# LTC4041_Battery_Power_Management_IC.net
KiCad netlist of a schematic drawn in Altium Designer
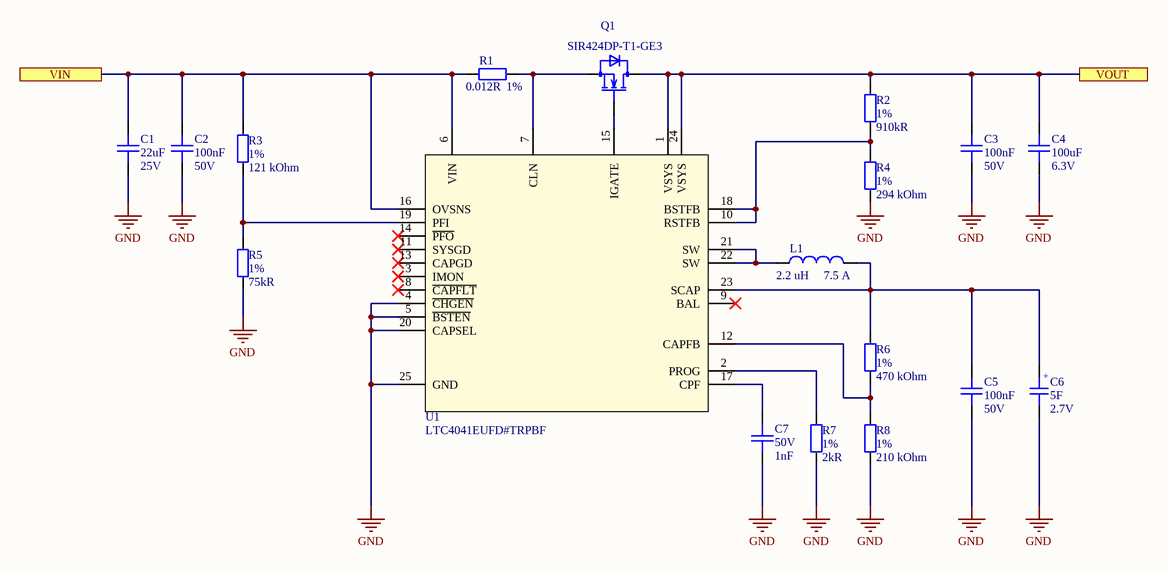
[diagram p0: LTC4041_Battery Power Management IC.SchDoc]

(export (version "E")
  (design (tool "Eeschema 10.0.6"))
  (components
    (comp (ref "C1")
      (value "CAP CER 22UF 25V X5R 0805")
      (footprint "C0805")
      (description "22µF ±20% 25V Ceramic Capacitor X5R 0805 (2012 Metric)")
      (fields
        (field (name "MANUFACTURER") "Yageo")
        (field (name "MANUFACTURER PART NUMBER") "CC0805MKX5R8BB226")
        (field (name "CAPACITANCE") "22uF")
        (field (name "VOLTAGE RATING") "25V")
      )
      (libsource (lib "Control_Board_Model") (part "CAP CER 22UF 25V X5R 0805"))
    )
    (comp (ref "C2")
      (value "CAP CER 0.1UF 50V X7R 0402")
      (footprint "C0402")
      (description "0.1µF ±10% 50V Ceramic Capacitor X7R 0402 (1005 Metric)")
      (fields
        (field (name "MANUFACTURER") "TDK")
        (field (name "MANUFACTURER PART NUMBER") "CGA2B3X7R1H104K050BB")
        (field (name "CAPACITANCE") "100nF")
        (field (name "VOLTAGE") "50V")
      )
      (libsource (lib "Control_Board_Model") (part "CAP CER 0.1UF 50V X7R 0402"))
    )
    (comp (ref "C3")
      (value "CAP CER 0.1UF 50V X7R 0402")
      (footprint "C0402")
      (description "0.1µF ±10% 50V Ceramic Capacitor X7R 0402 (1005 Metric)")
      (fields
        (field (name "MANUFACTURER") "TDK")
        (field (name "MANUFACTURER PART NUMBER") "CGA2B3X7R1H104K050BB")
        (field (name "CAPACITANCE") "100nF")
        (field (name "VOLTAGE") "50V")
      )
      (libsource (lib "Control_Board_Model") (part "CAP CER 0.1UF 50V X7R 0402"))
    )
    (comp (ref "C4")
      (value "CAP CER 100UF 6.3V X5R 1206")
      (footprint "C1206")
      (description "100 µF ±20% 6.3V Ceramic Capacitor X5R 1206 (3216 Metric)")
      (fields
        (field (name "MANUFACTURER") "Yageo")
        (field (name "MANUFACTURER PART NUMBER") "CC1206MKX5R5BB107")
        (field (name "CAPACITANCE") "100uF")
        (field (name "VOLTAGE RATING") "6.3V")
      )
      (libsource (lib "Control_Board_Model") (part "CAP CER 100UF 6.3V X5R 1206"))
    )
    (comp (ref "C5")
      (value "CAP CER 0.1UF 50V X7R 0402")
      (footprint "C0402")
      (description "0.1µF ±10% 50V Ceramic Capacitor X7R 0402 (1005 Metric)")
      (fields
        (field (name "MANUFACTURER") "TDK")
        (field (name "MANUFACTURER PART NUMBER") "CGA2B3X7R1H104K050BB")
        (field (name "CAPACITANCE") "100nF")
        (field (name "VOLTAGE") "50V")
      )
      (libsource (lib "Control_Board_Model") (part "CAP CER 0.1UF 50V X7R 0402"))
    )
    (comp (ref "C6")
      (value "CAP 5F 0% +100% 2.7V T/H")
      (footprint "CAPASITOR_10")
      (description "5 F (EDLC) Supercapacitor 2.7 V Radial, Can 70mOhm @ 1kHz 1000 Hrs @ 60°C")
      (fields
        (field (name "MANUFACTURER") "AVX Corporation")
        (field (name "MANUFACTURER PART NUMBER") "SCCS20B505PRB")
        (field (name "CAPACITANCE") "5F")
        (field (name "VOLTAGE RATING") "2.7V")
      )
      (libsource (lib "Control_Board_Model") (part "CAP 5F 0% +100% 2.7V T/H"))
    )
    (comp (ref "C7")
      (value "CAP CER 1000PF 50V X7R 0402")
      (footprint "C0402")
      (description "1000pF ±10% 50V Ceramic Capacitor X7R 0402 (1005 Metric)")
      (fields
        (field (name "MANUFACTURER") "TDK-Lambda")
        (field (name "MANUFACTURER PART NUMBER") "C0402C102K5RACTU")
        (field (name "VOLTAGE RATING (DC)") "50V")
        (field (name "CAPACITANCE") "1nF")
      )
      (libsource (lib "Control_Board_Model") (part "CAP CER 1000PF 50V X7R 0402"))
    )
    (comp (ref "L1")
      (value "FIXED IND 2.2UH 7.5A 16.1MOHM SM")
      (footprint "IND_WE_MAPI")
      (description "2.2 µH Shielded - Inductor 7.5 A 16.1mOhm Max Nonstandard -")
      (fields
        (field (name "MANUFACTURER") "Wurth Elektronik")
        (field (name "MANUFACTURER PART NUMBER") "74438367022")
        (field (name "INDUCTANCE") "2.2 uH")
        (field (name "MAXIMUM DC CURRENT") "7.5 A")
      )
      (libsource (lib "Control_Board_Model") (part "FIXED IND 2.2UH 7.5A 16.1MOHM SM"))
    )
    (comp (ref "Q1")
      (value "SIR424DP-T1-GE3")
      (footprint "PowerPAK® SO-8")
      (description "N-Channel 20 V 30A (Tc) 4.8W (Ta), 41.7W (Tc) Surface Mount PowerPAK® SO-8")
      (fields (field (name "MANUFACTURER") "Vishay Siliconix"))
      (libsource (lib "Control_Board_Model") (part "MOSFET N-CH 20V 30A PPAK SO-8"))
    )
    (comp (ref "R1")
      (value "RES 0.012 OHM 1% 3W 2512")
      (footprint "R2512")
      (description "12 mOhms ±1% 3W Chip Resistor 2512 (6432 Metric) Current Sense Metal Element")
      (fields
        (field (name "MANUFACTURER") "Stackpole Electronics Inc")
        (field (name "MANUFACTURER PART NUMBER") "CSM2512FT12L0")
        (field (name "TOLERANCE") "1%")
        (field (name "RESISTANCE") "0.012R")
      )
      (libsource (lib "Control_Board_Model") (part "RES 0.012 OHM 1% 3W 2512"))
    )
    (comp (ref "R2")
      (value "RES SMD 910K OHM 1% 1/16W 0402")
      (footprint "R0402")
      (description "910 kOhms ±1% 0.063W, 1/16W Chip Resistor 0402 (1005 Metric) Moisture Resistant Thick Film")
      (fields
        (field (name "MANUFACTURER") "Yageo")
        (field (name "MANUFACTURER PART NUMBER") "RC0402FR-07910KL")
        (field (name "TOLERANCE") "1%")
        (field (name "RESISTANCE") "910kR")
      )
      (libsource (lib "Control_Board_Model") (part "RES SMD 910K OHM 1% 1/16W 0402"))
    )
    (comp (ref "R3")
      (value "RES SMD 121K OHM 1% 1/16W 0402")
      (footprint "R0402")
      (description "121 kOhms ±1% 0.063W, 1/16W Chip Resistor 0402 (1005 Metric) Moisture Resistant Thick Film")
      (fields
        (field (name "MANUFACTURER") "Yageo")
        (field (name "MANUFACTURER PART NUMBER") "RC0402FR-07121KL")
        (field (name "TOLERANCE") "1%")
        (field (name "RESISTANCE") "121 kOhm")
      )
      (libsource (lib "Control_Board_Model") (part "RES SMD 121K OHM 1% 1/16W 0402"))
    )
    (comp (ref "R4")
      (value "RES SMD 294K OHM 1% 1/16W 0402")
      (footprint "R0402")
      (description "294 kOhms ±1% 0.063W, 1/16W Chip Resistor 0402 (1005 Metric) Moisture Resistant Thick Film")
      (fields
        (field (name "MANUFACTURER") "Yageo")
        (field (name "MANUFACTURER PART NUMBER") "RC0402FR-07294KL")
        (field (name "TOLERANCE") "1%")
        (field (name "RESISTANCE") "294 kOhm")
      )
      (libsource (lib "Control_Board_Model") (part "RES SMD 294K OHM 1% 1/16W 0402"))
    )
    (comp (ref "R5")
      (value "RES SMD 75K OHM 1% 1/16W 0402")
      (footprint "R0402")
      (description "75 kOhms ±1% 0.063W, 1/16W Chip Resistor 0402 (1005 Metric) Automotive AEC-Q200 Thick Film")
      (fields
        (field (name "MANUFACTURER") "Stackpole Electronics")
        (field (name "MANUFACTURER PART NUMBER") "RMCF0402FT75K0")
        (field (name "TOLERANCE") "1%")
        (field (name "RESISTANCE") "75kR")
      )
      (libsource (lib "Control_Board_Model") (part "RES SMD 75K OHM 1% 1/16W 0402"))
    )
    (comp (ref "R6")
      (value "RES SMD 470K OHM 1% 1/16W 0402")
      (footprint "R0402")
      (description "470 kOhms ±1% 0.063W, 1/16W Chip Resistor 0402 (1005 Metric) Moisture Resistant Thick Film")
      (fields
        (field (name "MANUFACTURER") "Yageo")
        (field (name "MANUFACTURER PART NUMBER") "RC0402FR-07470KL")
        (field (name "TOLERANCE") "1%")
        (field (name "RESISTANCE") "470 kOhm")
      )
      (libsource (lib "Control_Board_Model") (part "RES SMD 470K OHM 1% 1/16W 0402"))
    )
    (comp (ref "R7")
      (value "RC0402FR-072KL")
      (footprint "R0402")
      (description "2 kOhms ±1% 0.063W, 1/16W Chip Resistor 0402 (1005 Metric) Moisture Resistant Thick Film")
      (fields
        (field (name "MANUFACTURER") "Yageo")
        (field (name "TOLERANCE") "1%")
        (field (name "RESISTANCE") "2kR")
      )
      (libsource (lib "Control_Board_Model") (part "RES SMD 2K OHM 1% 1/16W 0402"))
    )
    (comp (ref "R8")
      (value "RES SMD 210K OHM 1% 1/16W 0402")
      (footprint "R0402")
      (description "210 kOhms ±1% 0.063W, 1/16W Chip Resistor 0402 (1005 Metric) Moisture Resistant Thick Film")
      (fields
        (field (name "MANUFACTURER") "Yageo")
        (field (name "MANUFACTURER PART NUMBER") "RC0402FR-07210KL")
        (field (name "TOLERANCE") "1%")
        (field (name "RESISTANCE") "210 kOhm")
      )
      (libsource (lib "Control_Board_Model") (part "RES SMD 210K OHM 1% 1/16W 0402"))
    )
    (comp (ref "U1")
      (value "LTC4041EUFD#TRPBF")
      (footprint "QFN24_4X5")
      (description "Battery Power Management IC Multi-Chemistry 24-QFN (4x5)")
      (fields (field (name "MANUFACTURER") "Analog Devices Inc."))
      (libsource (lib "Control_Board_Model") (part "IC LTC4041EUFD#TRPBF BATT PWR MGMT MULTI 1C 24QFN"))
    )
  )
  (nets
    (net (code "1") (name "/VIN") (class "Default")
      (node (ref "C1") (pin "2") (pinfunction "2_2") (pintype "passive"))
      (node (ref "C2") (pin "2") (pinfunction "2_2") (pintype "passive"))
      (node (ref "R1") (pin "1") (pinfunction "1_1") (pintype "passive"))
      (node (ref "R3") (pin "2") (pinfunction "2_2") (pintype "passive"))
      (node (ref "U1") (pin "16") (pinfunction "OVSNS_16") (pintype "power_in"))
      (node (ref "U1") (pin "6") (pinfunction "VIN_6") (pintype "power_in"))
    )
    (net (code "2") (name "/VOUT") (class "Default")
      (node (ref "C3") (pin "2") (pinfunction "2_2") (pintype "passive"))
      (node (ref "C4") (pin "2") (pinfunction "2_2") (pintype "passive"))
      (node (ref "Q1") (pin "3") (pinfunction "D_3") (pintype "passive"))
      (node (ref "R2") (pin "1") (pinfunction "1_1") (pintype "passive"))
      (node (ref "U1") (pin "1") (pinfunction "VSYS_1") (pintype "power_in"))
      (node (ref "U1") (pin "24") (pinfunction "VSYS_24") (pintype "power_in"))
    )
    (net (code "3") (name "GND") (class "Default")
      (node (ref "C1") (pin "1") (pinfunction "1_1") (pintype "passive"))
      (node (ref "C2") (pin "1") (pinfunction "1_1") (pintype "passive"))
      (node (ref "C3") (pin "1") (pinfunction "1_1") (pintype "passive"))
      (node (ref "C4") (pin "1") (pinfunction "1_1") (pintype "passive"))
      (node (ref "C5") (pin "1") (pinfunction "1_1") (pintype "passive"))
      (node (ref "C6") (pin "2") (pinfunction "2_2") (pintype "passive"))
      (node (ref "C7") (pin "1") (pinfunction "1_1") (pintype "passive"))
      (node (ref "R4") (pin "1") (pinfunction "1_1") (pintype "passive"))
      (node (ref "R5") (pin "1") (pinfunction "1_1") (pintype "passive"))
      (node (ref "R7") (pin "1") (pinfunction "1_1") (pintype "passive"))
      (node (ref "R8") (pin "1") (pinfunction "1_1") (pintype "passive"))
      (node (ref "U1") (pin "20") (pinfunction "CAPSEL_20") (pintype "power_in"))
      (node (ref "U1") (pin "25") (pinfunction "GND_25") (pintype "power_in"))
      (node (ref "U1") (pin "4") (pinfunction "~{CHGEN}_4") (pintype "power_in"))
      (node (ref "U1") (pin "5") (pinfunction "~{BSTEN}_5") (pintype "power_in"))
    )
    (net (code "4") (name "Net-(L1-Pad1)") (class "Default")
      (node (ref "L1") (pin "1") (pinfunction "1_1") (pintype "passive"))
      (node (ref "U1") (pin "21") (pinfunction "SW_21") (pintype "power_in"))
      (node (ref "U1") (pin "22") (pinfunction "SW_22") (pintype "power_in"))
    )
    (net (code "5") (name "Net-(Q1-G)") (class "Default")
      (node (ref "Q1") (pin "1") (pinfunction "G_1") (pintype "passive"))
      (node (ref "U1") (pin "15") (pinfunction "IGATE_15") (pintype "power_in"))
    )
    (net (code "6") (name "Net-(Q1-S)") (class "Default")
      (node (ref "Q1") (pin "2") (pinfunction "S_2") (pintype "passive"))
      (node (ref "R1") (pin "2") (pinfunction "2_2") (pintype "passive"))
      (node (ref "U1") (pin "7") (pinfunction "CLN_7") (pintype "power_in"))
    )
    (net (code "7") (name "Net-(U1-BSTFB)") (class "Default")
      (node (ref "R2") (pin "2") (pinfunction "2_2") (pintype "passive"))
      (node (ref "R4") (pin "2") (pinfunction "2_2") (pintype "passive"))
      (node (ref "U1") (pin "10") (pinfunction "RSTFB_10") (pintype "power_in"))
      (node (ref "U1") (pin "18") (pinfunction "BSTFB_18") (pintype "power_in"))
    )
    (net (code "8") (name "Net-(U1-CAPFB)") (class "Default")
      (node (ref "R6") (pin "1") (pinfunction "1_1") (pintype "passive"))
      (node (ref "R8") (pin "2") (pinfunction "2_2") (pintype "passive"))
      (node (ref "U1") (pin "12") (pinfunction "CAPFB_12") (pintype "power_in"))
    )
    (net (code "9") (name "Net-(U1-CPF)") (class "Default")
      (node (ref "C7") (pin "2") (pinfunction "2_2") (pintype "passive"))
      (node (ref "U1") (pin "17") (pinfunction "CPF_17") (pintype "power_in"))
    )
    (net (code "10") (name "Net-(U1-PFI)") (class "Default")
      (node (ref "R3") (pin "1") (pinfunction "1_1") (pintype "passive"))
      (node (ref "R5") (pin "2") (pinfunction "2_2") (pintype "passive"))
      (node (ref "U1") (pin "19") (pinfunction "PFI_19") (pintype "power_in"))
    )
    (net (code "11") (name "Net-(U1-PROG)") (class "Default")
      (node (ref "R7") (pin "2") (pinfunction "2_2") (pintype "passive"))
      (node (ref "U1") (pin "2") (pinfunction "PROG_2") (pintype "power_in"))
    )
    (net (code "12") (name "Net-(U1-SCAP)") (class "Default")
      (node (ref "C5") (pin "2") (pinfunction "2_2") (pintype "passive"))
      (node (ref "C6") (pin "1") (pinfunction "1_1") (pintype "passive"))
      (node (ref "L1") (pin "2") (pinfunction "2_2") (pintype "passive"))
      (node (ref "R6") (pin "2") (pinfunction "2_2") (pintype "passive"))
      (node (ref "U1") (pin "23") (pinfunction "SCAP_23") (pintype "power_in"))
    )
    (net (code "13") (name "unconnected-(U1-BAL-Pad9)") (class "Default")
      (node (ref "U1") (pin "9") (pinfunction "BAL_9") (pintype "power_in+no_connect"))
    )
    (net (code "14") (name "unconnected-(U1-CAPGD-Pad13)") (class "Default")
      (node (ref "U1") (pin "13") (pinfunction "CAPGD_13") (pintype "power_in+no_connect"))
    )
    (net (code "15") (name "unconnected-(U1-IMON-Pad3)") (class "Default")
      (node (ref "U1") (pin "3") (pinfunction "IMON_3") (pintype "power_in+no_connect"))
    )
    (net (code "16") (name "unconnected-(U1-SYSGD-Pad11)") (class "Default")
      (node (ref "U1") (pin "11") (pinfunction "SYSGD_11") (pintype "power_in+no_connect"))
    )
    (net (code "17") (name "unconnected-(U1-~{CAPFLT}-Pad8)") (class "Default")
      (node (ref "U1") (pin "8") (pinfunction "~{CAPFLT}_8") (pintype "power_in+no_connect"))
    )
    (net (code "18") (name "unconnected-(U1-~{PFO}-Pad14)") (class "Default")
      (node (ref "U1") (pin "14") (pinfunction "~{PFO}_14") (pintype "power_in+no_connect"))
    )
  )
)
